# wifi_agronautes.net
KiCad netlist of a schematic drawn in EAGLE
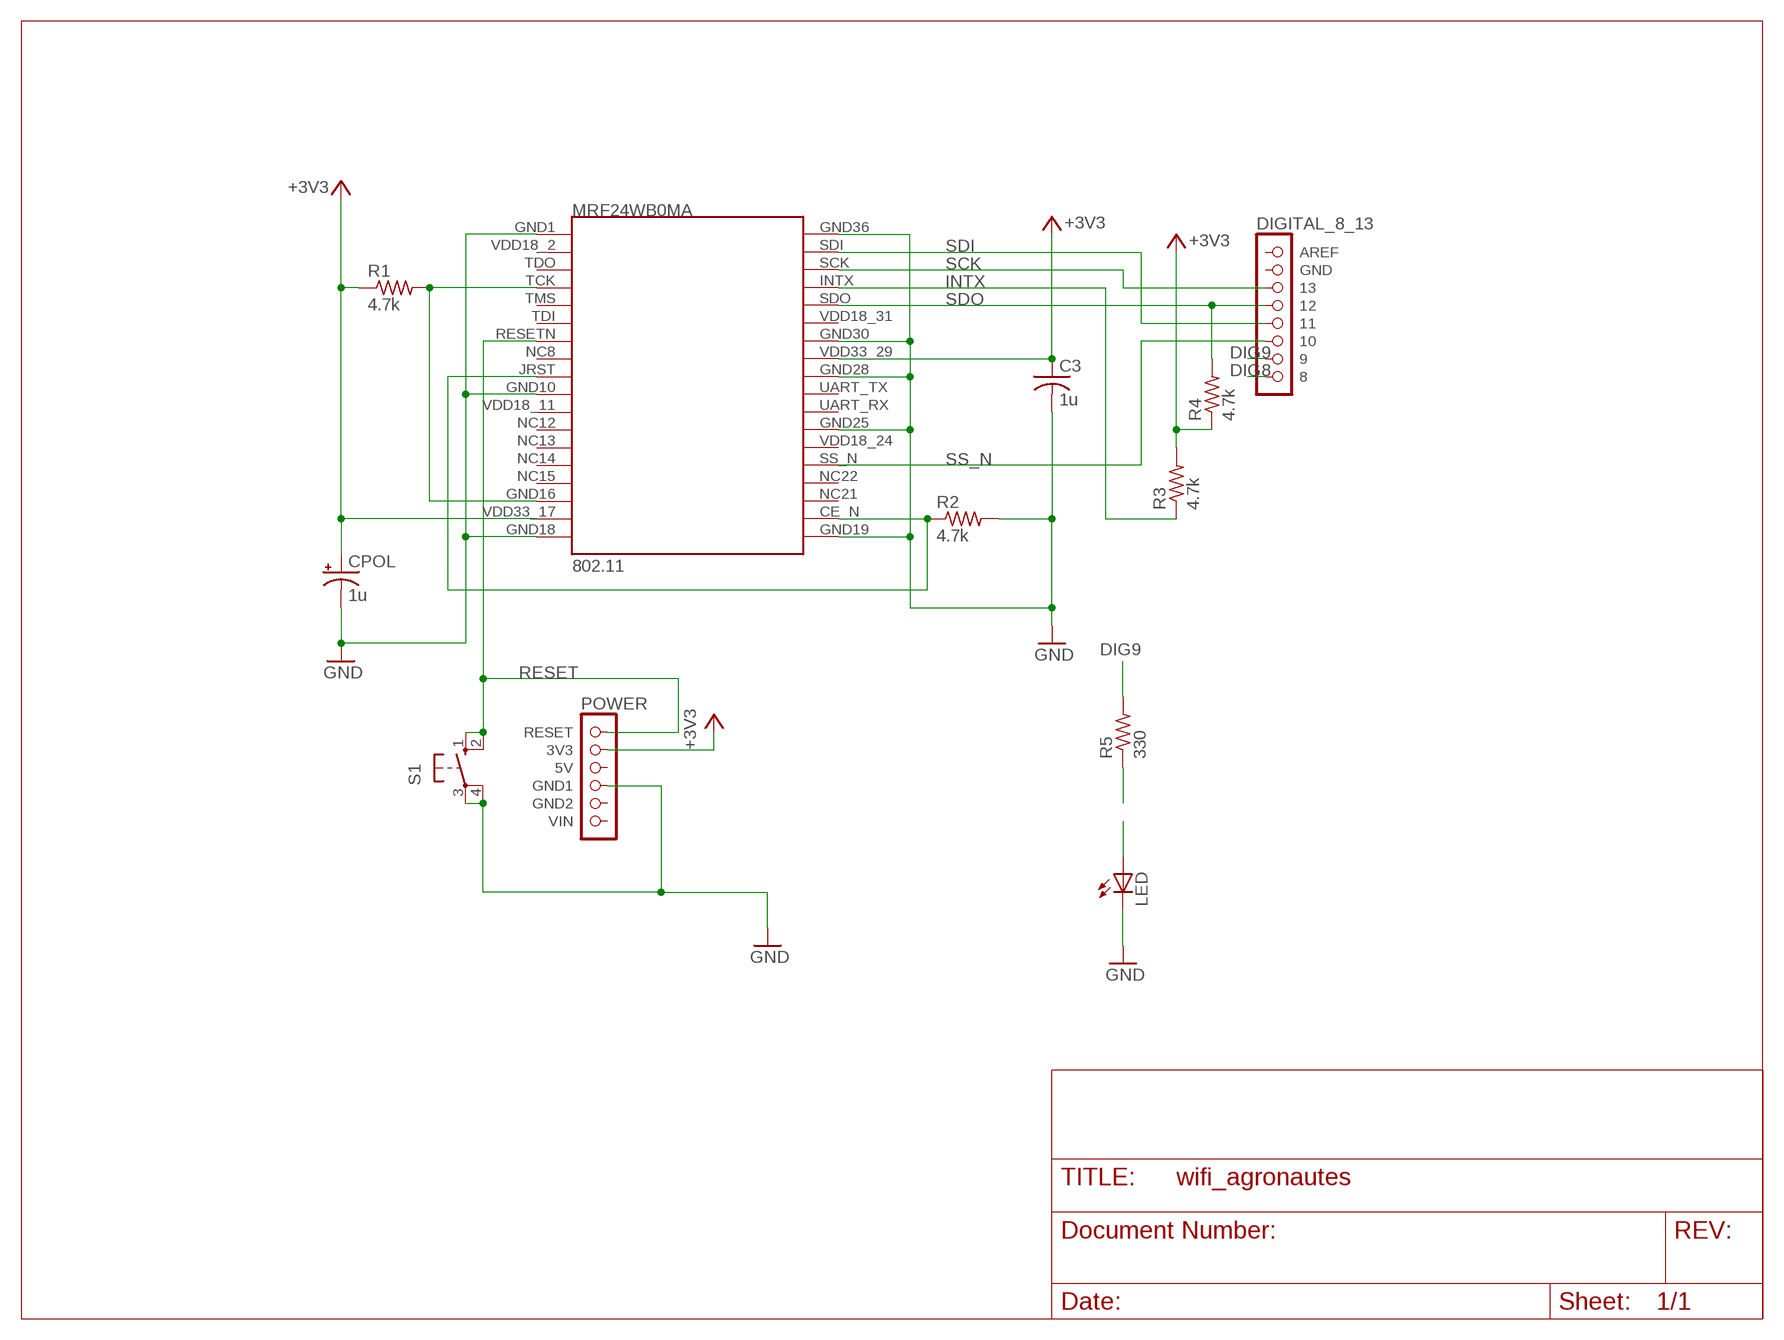
[diagram p0: schematic, sheet 1]

(export (version "E")
  (design (tool "Eeschema 10.0.6"))
  (components
    (comp (ref "C3")
      (value "1u")
      (footprint "eagle-import:CAP")
      (libsource (lib "eagle-import") (part "CAP"))
    )
    (comp (ref "CPOL")
      (value "1u")
      (footprint "eagle-import:PCAP")
      (libsource (lib "eagle-import") (part "PCAP"))
    )
    (comp (ref "LED")
      (value "LED3MM")
      (footprint "eagle-import:LED3MM")
      (libsource (lib "eagle-import") (part "LED3MM"))
    )
    (comp (ref "MRF24WB0MA")
      (value "802.11")
      (footprint "eagle-import:ZG2100MOD")
      (libsource (lib "eagle-import") (part "ZG2100MOD"))
    )
    (comp (ref "R1")
      (value "4.7k")
      (footprint "eagle-import:RES_SMALL")
      (libsource (lib "eagle-import") (part "RES_SMALL"))
    )
    (comp (ref "R2")
      (value "4.7k")
      (footprint "eagle-import:RES_SMALL")
      (libsource (lib "eagle-import") (part "RES_SMALL"))
    )
    (comp (ref "R3")
      (value "4.7k")
      (footprint "eagle-import:RES_SMALL")
      (libsource (lib "eagle-import") (part "RES_SMALL"))
    )
    (comp (ref "R4")
      (value "4.7k")
      (footprint "eagle-import:RES")
      (libsource (lib "eagle-import") (part "RES"))
    )
    (comp (ref "R5")
      (value "330")
      (footprint "eagle-import:RES_SMALL")
      (libsource (lib "eagle-import") (part "RES_SMALL"))
    )
    (comp (ref "S1")
      (value "SWITCH")
      (footprint "eagle-import:SWITCH")
      (libsource (lib "eagle-import") (part "SWITCH"))
    )
    (comp (ref "U$1")
      (value "POWER")
      (footprint "eagle-import:1X06")
      (libsource (lib "eagle-import") (part "POWER"))
    )
    (comp (ref "U$4")
      (value "DIGITAL_8_13")
      (footprint "eagle-import:1X08")
      (libsource (lib "eagle-import") (part "DIGITAL_8_13"))
    )
  )
  (nets
    (net (code "1") (name "+3V3") (class "Default")
      (node (ref "C3") (pin "1") (pinfunction "1_1") (pintype "passive"))
      (node (ref "CPOL") (pin "+") (pinfunction "+_+") (pintype "passive"))
      (node (ref "MRF24WB0MA") (pin "VDD33_17") (pinfunction "VDD33_17_VDD33_17") (pintype "power_in"))
      (node (ref "MRF24WB0MA") (pin "VDD33_29") (pinfunction "VDD33_29_VDD33_29") (pintype "power_in"))
      (node (ref "R1") (pin "1") (pinfunction "1_1") (pintype "passive"))
      (node (ref "R3") (pin "2") (pinfunction "2_2") (pintype "passive"))
      (node (ref "R4") (pin "1") (pinfunction "1_1") (pintype "passive"))
      (node (ref "U$1") (pin "2") (pinfunction "3V3_2") (pintype "passive"))
    )
    (net (code "2") (name "/DIG8") (class "Default")
      (node (ref "U$4") (pin "8") (pinfunction "8_8") (pintype "passive"))
    )
    (net (code "3") (name "/DIG9") (class "Default")
      (node (ref "R5") (pin "2") (pinfunction "2_2") (pintype "passive"))
      (node (ref "U$4") (pin "7") (pinfunction "9_7") (pintype "passive"))
    )
    (net (code "4") (name "/INTX") (class "Default")
      (node (ref "MRF24WB0MA") (pin "INTX") (pinfunction "INTX_INTX") (pintype "output"))
      (node (ref "R3") (pin "1") (pinfunction "1_1") (pintype "passive"))
    )
    (net (code "5") (name "/RESET") (class "Default")
      (node (ref "MRF24WB0MA") (pin "RESETN") (pinfunction "RSTN_RESETN") (pintype "input"))
      (node (ref "S1") (pin "1") (pinfunction "S_1") (pintype "passive"))
      (node (ref "S1") (pin "2") (pinfunction "S1_2") (pintype "passive"))
      (node (ref "U$1") (pin "1") (pinfunction "RESET_1") (pintype "passive"))
    )
    (net (code "6") (name "/SCK") (class "Default")
      (node (ref "MRF24WB0MA") (pin "SCK") (pinfunction "SCK_SCK") (pintype "input"))
      (node (ref "U$4") (pin "3") (pinfunction "13_3") (pintype "passive"))
    )
    (net (code "7") (name "/SDI") (class "Default")
      (node (ref "MRF24WB0MA") (pin "SDI") (pinfunction "SDI_SDI") (pintype "input"))
      (node (ref "U$4") (pin "5") (pinfunction "11_5") (pintype "passive"))
    )
    (net (code "8") (name "/SDO") (class "Default")
      (node (ref "MRF24WB0MA") (pin "SDO") (pinfunction "SDO_SDO") (pintype "output"))
      (node (ref "R4") (pin "2") (pinfunction "2_2") (pintype "passive"))
      (node (ref "U$4") (pin "4") (pinfunction "12_4") (pintype "passive"))
    )
    (net (code "9") (name "/SS_N") (class "Default")
      (node (ref "MRF24WB0MA") (pin "SS_N") (pinfunction "SS_N_SS_N") (pintype "input"))
      (node (ref "U$4") (pin "6") (pinfunction "10_6") (pintype "passive"))
    )
    (net (code "10") (name "GND") (class "Default")
      (node (ref "C3") (pin "2") (pinfunction "2_2") (pintype "passive"))
      (node (ref "CPOL") (pin "-") (pinfunction "-_-") (pintype "passive"))
      (node (ref "LED") (pin "K") (pinfunction "C_K") (pintype "passive"))
      (node (ref "MRF24WB0MA") (pin "GND1") (pinfunction "GND1_GND1") (pintype "power_in"))
      (node (ref "MRF24WB0MA") (pin "GND10") (pinfunction "GND10_GND10") (pintype "power_in"))
      (node (ref "MRF24WB0MA") (pin "GND18") (pinfunction "GND18_GND18") (pintype "power_in"))
      (node (ref "MRF24WB0MA") (pin "GND19") (pinfunction "GND19_GND19") (pintype "power_in"))
      (node (ref "MRF24WB0MA") (pin "GND25") (pinfunction "GND25_GND25") (pintype "power_in"))
      (node (ref "MRF24WB0MA") (pin "GND28") (pinfunction "GND28_GND28") (pintype "bidirectional"))
      (node (ref "MRF24WB0MA") (pin "GND30") (pinfunction "GND30_GND30") (pintype "power_in"))
      (node (ref "MRF24WB0MA") (pin "GND36") (pinfunction "GND36_GND36") (pintype "bidirectional"))
      (node (ref "R2") (pin "2") (pinfunction "2_2") (pintype "passive"))
      (node (ref "S1") (pin "3") (pinfunction "P_3") (pintype "passive"))
      (node (ref "S1") (pin "4") (pinfunction "P1_4") (pintype "passive"))
      (node (ref "U$1") (pin "4") (pinfunction "GND1_4") (pintype "passive"))
    )
    (net (code "11") (name "Net-(MRF24WB0MA-PadCE_N)") (class "Default")
      (node (ref "MRF24WB0MA") (pin "CE_N") (pinfunction "CE_N_CE_N") (pintype "input"))
      (node (ref "MRF24WB0MA") (pin "JRST") (pinfunction "JRST_JRST") (pintype "input"))
      (node (ref "R2") (pin "1") (pinfunction "1_1") (pintype "passive"))
    )
    (net (code "12") (name "Net-(MRF24WB0MA-PadGND16)") (class "Default")
      (node (ref "MRF24WB0MA") (pin "GND16") (pinfunction "GND16_GND16") (pintype "power_in"))
      (node (ref "MRF24WB0MA") (pin "TCK") (pinfunction "TCK_TCK") (pintype "bidirectional"))
      (node (ref "R1") (pin "2") (pinfunction "2_2") (pintype "passive"))
    )
    (net (code "13") (name "unconnected-(LED-PadA)") (class "Default")
      (node (ref "LED") (pin "A") (pinfunction "A_A") (pintype "passive"))
    )
    (net (code "14") (name "unconnected-(MRF24WB0MA-PadNC8)") (class "Default")
      (node (ref "MRF24WB0MA") (pin "NC8") (pinfunction "NC8_NC8") (pintype "no_connect"))
    )
    (net (code "15") (name "unconnected-(MRF24WB0MA-PadNC12)") (class "Default")
      (node (ref "MRF24WB0MA") (pin "NC12") (pinfunction "NC12_NC12") (pintype "no_connect"))
    )
    (net (code "16") (name "unconnected-(MRF24WB0MA-PadNC13)") (class "Default")
      (node (ref "MRF24WB0MA") (pin "NC13") (pinfunction "NC13_NC13") (pintype "no_connect"))
    )
    (net (code "17") (name "unconnected-(MRF24WB0MA-PadNC14)") (class "Default")
      (node (ref "MRF24WB0MA") (pin "NC14") (pinfunction "NC14_NC14") (pintype "no_connect"))
    )
    (net (code "18") (name "unconnected-(MRF24WB0MA-PadNC15)") (class "Default")
      (node (ref "MRF24WB0MA") (pin "NC15") (pinfunction "NC15_NC15") (pintype "no_connect"))
    )
    (net (code "19") (name "unconnected-(MRF24WB0MA-PadNC21)") (class "Default")
      (node (ref "MRF24WB0MA") (pin "NC21") (pinfunction "NC21_NC21") (pintype "no_connect"))
    )
    (net (code "20") (name "unconnected-(MRF24WB0MA-PadNC22)") (class "Default")
      (node (ref "MRF24WB0MA") (pin "NC22") (pinfunction "NC22_NC22") (pintype "no_connect"))
    )
    (net (code "21") (name "unconnected-(MRF24WB0MA-PadTDI)") (class "Default")
      (node (ref "MRF24WB0MA") (pin "TDI") (pinfunction "TDI_TDI") (pintype "no_connect"))
    )
    (net (code "22") (name "unconnected-(MRF24WB0MA-PadTDO)") (class "Default")
      (node (ref "MRF24WB0MA") (pin "TDO") (pinfunction "TDO_TDO") (pintype "output"))
    )
    (net (code "23") (name "unconnected-(MRF24WB0MA-PadTMS)") (class "Default")
      (node (ref "MRF24WB0MA") (pin "TMS") (pinfunction "TMS_TMS") (pintype "no_connect"))
    )
    (net (code "24") (name "unconnected-(MRF24WB0MA-PadUART_RX)") (class "Default")
      (node (ref "MRF24WB0MA") (pin "UART_RX") (pinfunction "UART_RX_UART_RX") (pintype "bidirectional"))
    )
    (net (code "25") (name "unconnected-(MRF24WB0MA-PadUART_TX)") (class "Default")
      (node (ref "MRF24WB0MA") (pin "UART_TX") (pinfunction "UART_TX_UART_TX") (pintype "bidirectional"))
    )
    (net (code "26") (name "unconnected-(MRF24WB0MA-PadVDD18_2)") (class "Default")
      (node (ref "MRF24WB0MA") (pin "VDD18_2") (pinfunction "VDD18_2_VDD18_2") (pintype "no_connect"))
    )
    (net (code "27") (name "unconnected-(MRF24WB0MA-PadVDD18_11)") (class "Default")
      (node (ref "MRF24WB0MA") (pin "VDD18_11") (pinfunction "VDD18_11_VDD18_11") (pintype "no_connect"))
    )
    (net (code "28") (name "unconnected-(MRF24WB0MA-PadVDD18_24)") (class "Default")
      (node (ref "MRF24WB0MA") (pin "VDD18_24") (pinfunction "VDD18_24_VDD18_24") (pintype "no_connect"))
    )
    (net (code "29") (name "unconnected-(MRF24WB0MA-PadVDD18_31)") (class "Default")
      (node (ref "MRF24WB0MA") (pin "VDD18_31") (pinfunction "VDD18_31_VDD18_31") (pintype "no_connect"))
    )
    (net (code "30") (name "unconnected-(R5-Pad1)") (class "Default")
      (node (ref "R5") (pin "1") (pinfunction "1_1") (pintype "passive"))
    )
    (net (code "31") (name "unconnected-(U$1-5V-Pad3)") (class "Default")
      (node (ref "U$1") (pin "3") (pinfunction "5V_3") (pintype "passive"))
    )
    (net (code "32") (name "unconnected-(U$1-GND2-Pad5)") (class "Default")
      (node (ref "U$1") (pin "5") (pinfunction "GND2_5") (pintype "passive"))
    )
    (net (code "33") (name "unconnected-(U$1-VIN-Pad6)") (class "Default")
      (node (ref "U$1") (pin "6") (pinfunction "VIN_6") (pintype "passive"))
    )
    (net (code "34") (name "unconnected-(U$4-AREF-Pad1)") (class "Default")
      (node (ref "U$4") (pin "1") (pinfunction "AREF_1") (pintype "passive"))
    )
    (net (code "35") (name "unconnected-(U$4-GND-Pad2)") (class "Default")
      (node (ref "U$4") (pin "2") (pinfunction "GND_2") (pintype "passive"))
    )
  )
)
